# USB_mini_board.net
KiCad netlist of a schematic drawn in EAGLE
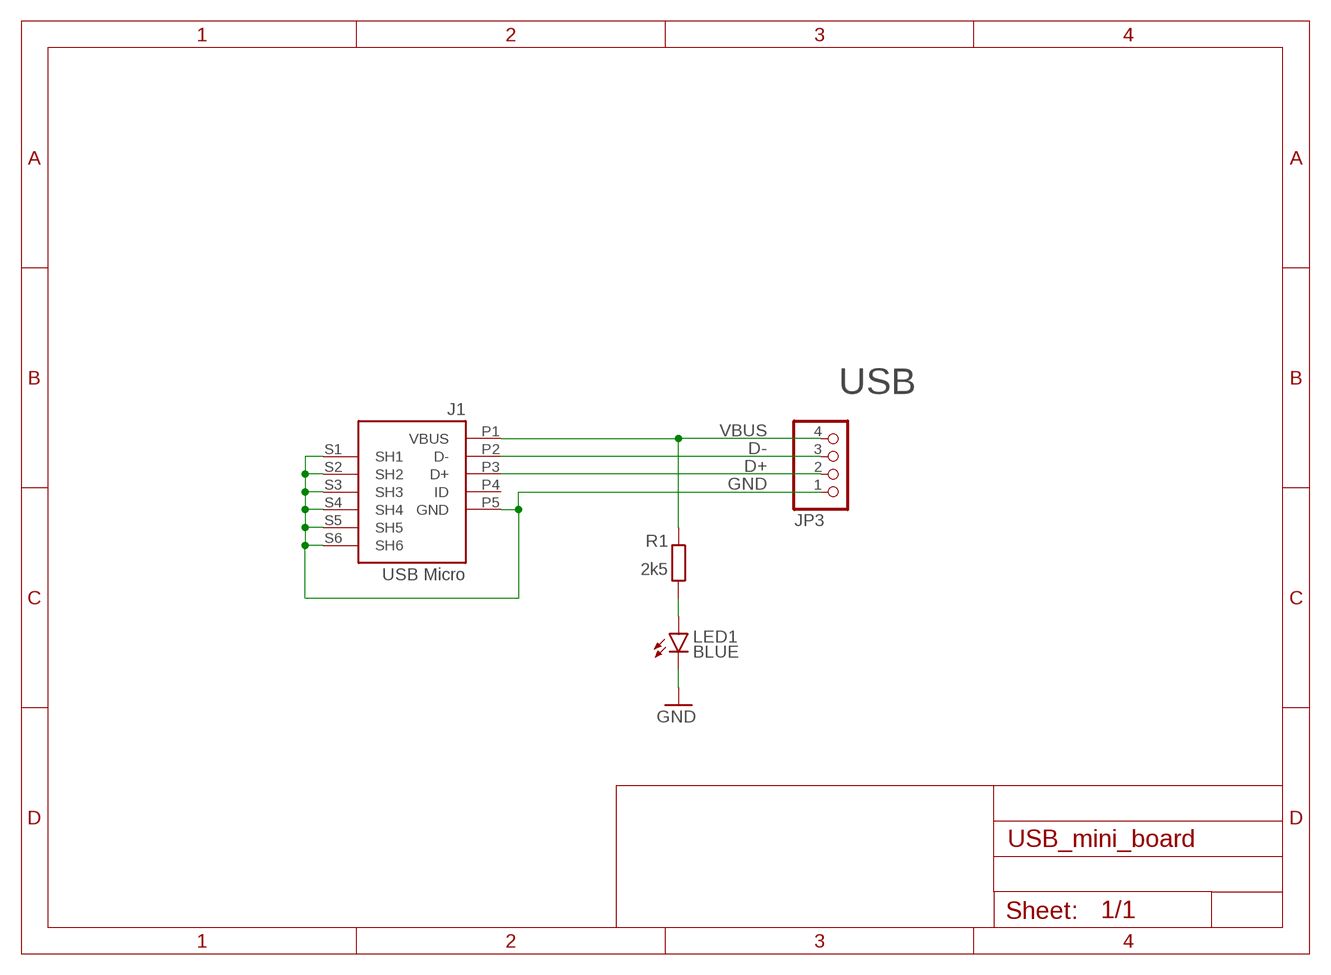
[diagram p0: schematic, sheet 1]

(export (version "E")
  (design (tool "Eeschema 10.0.6"))
  (components
    (comp (ref "J1")
      (value "USB Micro")
      (footprint "eagle-import:CON2_USB_MICRO_B_AT")
      (fields (field (name "MANUFACTURER") "FCI"))
      (libsource (lib "eagle-import") (part "USB-MICRO-LEGACY"))
    )
    (comp (ref "JP3")
      (value "PINHD-1X4")
      (footprint "eagle-import:1X04")
      (libsource (lib "eagle-import") (part "PINHD-1X4"))
    )
    (comp (ref "LED1")
      (value "BLUE")
      (footprint "eagle-import:CHIP-LED0805")
      (libsource (lib "eagle-import") (part "LEDCHIP-LED0805"))
    )
    (comp (ref "R1")
      (value "2k5")
      (footprint "eagle-import:R1206")
      (libsource (lib "eagle-import") (part "R-EU_R1206"))
    )
  )
  (nets
    (net (code "1") (name "/D+") (class "Default")
      (node (ref "J1") (pin "P3") (pinfunction "D+_P3") (pintype "bidirectional"))
      (node (ref "JP3") (pin "2") (pinfunction "2_2") (pintype "passive"))
    )
    (net (code "2") (name "/D-") (class "Default")
      (node (ref "J1") (pin "P2") (pinfunction "D-_P2") (pintype "bidirectional"))
      (node (ref "JP3") (pin "3") (pinfunction "3_3") (pintype "passive"))
    )
    (net (code "3") (name "/VBUS") (class "Default")
      (node (ref "J1") (pin "P1") (pinfunction "VBUS_P1") (pintype "power_in"))
      (node (ref "JP3") (pin "4") (pinfunction "4_4") (pintype "passive"))
      (node (ref "R1") (pin "1") (pinfunction "1_1") (pintype "passive"))
    )
    (net (code "4") (name "GND") (class "Default")
      (node (ref "J1") (pin "P5") (pinfunction "GND_P5") (pintype "passive"))
      (node (ref "J1") (pin "S1") (pinfunction "SH1_S1") (pintype "passive"))
      (node (ref "J1") (pin "S2") (pinfunction "SH2_S2") (pintype "passive"))
      (node (ref "J1") (pin "S3") (pinfunction "SH3_S3") (pintype "passive"))
      (node (ref "J1") (pin "S4") (pinfunction "SH4_S4") (pintype "passive"))
      (node (ref "J1") (pin "S5") (pinfunction "SH5_S5") (pintype "passive"))
      (node (ref "J1") (pin "S6") (pinfunction "SH6_S6") (pintype "passive"))
      (node (ref "JP3") (pin "1") (pinfunction "1_1") (pintype "passive"))
      (node (ref "LED1") (pin "C") (pinfunction "C_C") (pintype "passive"))
    )
    (net (code "5") (name "Net-(LED1-PadA)") (class "Default")
      (node (ref "LED1") (pin "A") (pinfunction "A_A") (pintype "passive"))
      (node (ref "R1") (pin "2") (pinfunction "2_2") (pintype "passive"))
    )
    (net (code "6") (name "unconnected-(J1-ID-PadP4)") (class "Default")
      (node (ref "J1") (pin "P4") (pinfunction "ID_P4") (pintype "bidirectional"))
    )
  )
)
